# Regulators.net
KiCad netlist of a schematic drawn in Altium Designer
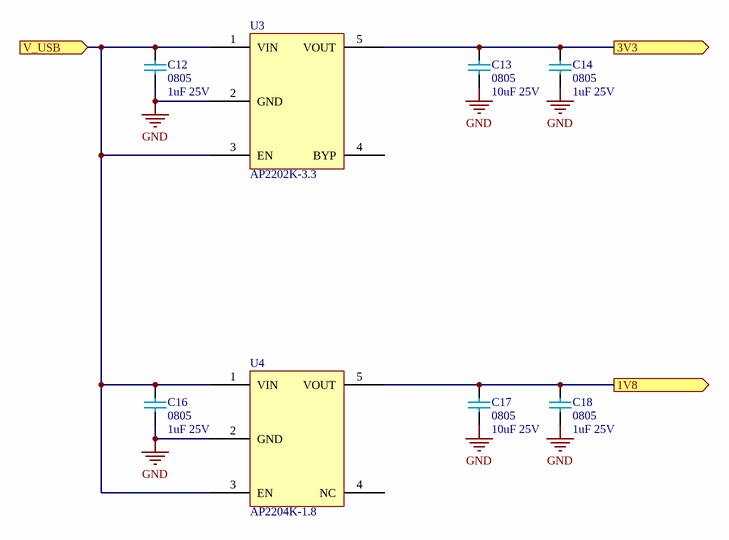
[diagram p0: Regulators.SchDoc]

(export (version "E")
  (design (tool "Eeschema 10.0.6"))
  (components
    (comp (ref "C12")
      (value "0805")
      (footprint "0805")
      (description "0805, X5R or better")
      (fields (field (name "ALTIUM_VALUE") "1uF 25V"))
      (libsource (lib "Chip_Passives") (part "Cap 1uF 25V"))
    )
    (comp (ref "C13")
      (value "0805")
      (footprint "0805")
      (description "0805, X5R or better")
      (fields (field (name "ALTIUM_VALUE") "10uF 25V"))
      (libsource (lib "Chip_Passives") (part "Cap 10uF 25V"))
    )
    (comp (ref "C14")
      (value "0805")
      (footprint "0805")
      (description "0805, X5R or better")
      (fields (field (name "ALTIUM_VALUE") "1uF 25V"))
      (libsource (lib "Chip_Passives") (part "Cap 1uF 25V"))
    )
    (comp (ref "C16")
      (value "0805")
      (footprint "0805")
      (description "0805, X5R or better")
      (fields (field (name "ALTIUM_VALUE") "1uF 25V"))
      (libsource (lib "Chip_Passives") (part "Cap 1uF 25V"))
    )
    (comp (ref "C17")
      (value "0805")
      (footprint "0805")
      (description "0805, X5R or better")
      (fields (field (name "ALTIUM_VALUE") "10uF 25V"))
      (libsource (lib "Chip_Passives") (part "Cap 10uF 25V"))
    )
    (comp (ref "C18")
      (value "0805")
      (footprint "0805")
      (description "0805, X5R or better")
      (fields (field (name "ALTIUM_VALUE") "1uF 25V"))
      (libsource (lib "Chip_Passives") (part "Cap 1uF 25V"))
    )
    (comp (ref "U3")
      (value "AP2202K-3.3")
      (footprint "AP2202 - SOT95P270X145-5N")
      (description "3.3V 150mA LDO regulator")
      (libsource (lib "PowerSupply") (part "AP2202K-3.3"))
    )
    (comp (ref "U4")
      (value "AP2204K-1.8")
      (footprint "AP2202 - SOT95P270X145-5N")
      (description "Linear Voltage Regulator IC 1 Output 150mA SOT-23-5")
      (libsource (lib "PowerSupply") (part "AP2204K-1.8"))
    )
  )
  (nets
    (net (code "1") (name "/1V8") (class "Default")
      (node (ref "C17") (pin "2") (pinfunction "2_2") (pintype "passive"))
      (node (ref "C18") (pin "2") (pinfunction "2_2") (pintype "passive"))
      (node (ref "U4") (pin "5") (pinfunction "VOUT_5") (pintype "passive"))
    )
    (net (code "2") (name "/3V3") (class "Default")
      (node (ref "C13") (pin "2") (pinfunction "2_2") (pintype "passive"))
      (node (ref "C14") (pin "2") (pinfunction "2_2") (pintype "passive"))
      (node (ref "U3") (pin "5") (pinfunction "VOUT_5") (pintype "passive"))
    )
    (net (code "3") (name "/V_USB") (class "Default")
      (node (ref "C12") (pin "2") (pinfunction "2_2") (pintype "passive"))
      (node (ref "C16") (pin "2") (pinfunction "2_2") (pintype "passive"))
      (node (ref "U3") (pin "1") (pinfunction "VIN_1") (pintype "passive"))
      (node (ref "U3") (pin "3") (pinfunction "EN_3") (pintype "passive"))
      (node (ref "U4") (pin "1") (pinfunction "VIN_1") (pintype "passive"))
      (node (ref "U4") (pin "3") (pinfunction "EN_3") (pintype "passive"))
    )
    (net (code "4") (name "GND") (class "Default")
      (node (ref "C12") (pin "1") (pinfunction "1_1") (pintype "passive"))
      (node (ref "C13") (pin "1") (pinfunction "1_1") (pintype "passive"))
      (node (ref "C14") (pin "1") (pinfunction "1_1") (pintype "passive"))
      (node (ref "C16") (pin "1") (pinfunction "1_1") (pintype "passive"))
      (node (ref "C17") (pin "1") (pinfunction "1_1") (pintype "passive"))
      (node (ref "C18") (pin "1") (pinfunction "1_1") (pintype "passive"))
      (node (ref "U3") (pin "2") (pinfunction "GND_2") (pintype "passive"))
      (node (ref "U4") (pin "2") (pinfunction "GND_2") (pintype "passive"))
    )
    (net (code "5") (name "unconnected-(U3-BYP-Pad4)") (class "Default")
      (node (ref "U3") (pin "4") (pinfunction "BYP_4") (pintype "passive"))
    )
    (net (code "6") (name "unconnected-(U4-NC-Pad4)") (class "Default")
      (node (ref "U4") (pin "4") (pinfunction "NC_4") (pintype "passive"))
    )
  )
)
